# LPC1343.net
KiCad netlist of a schematic drawn in Altium Designer
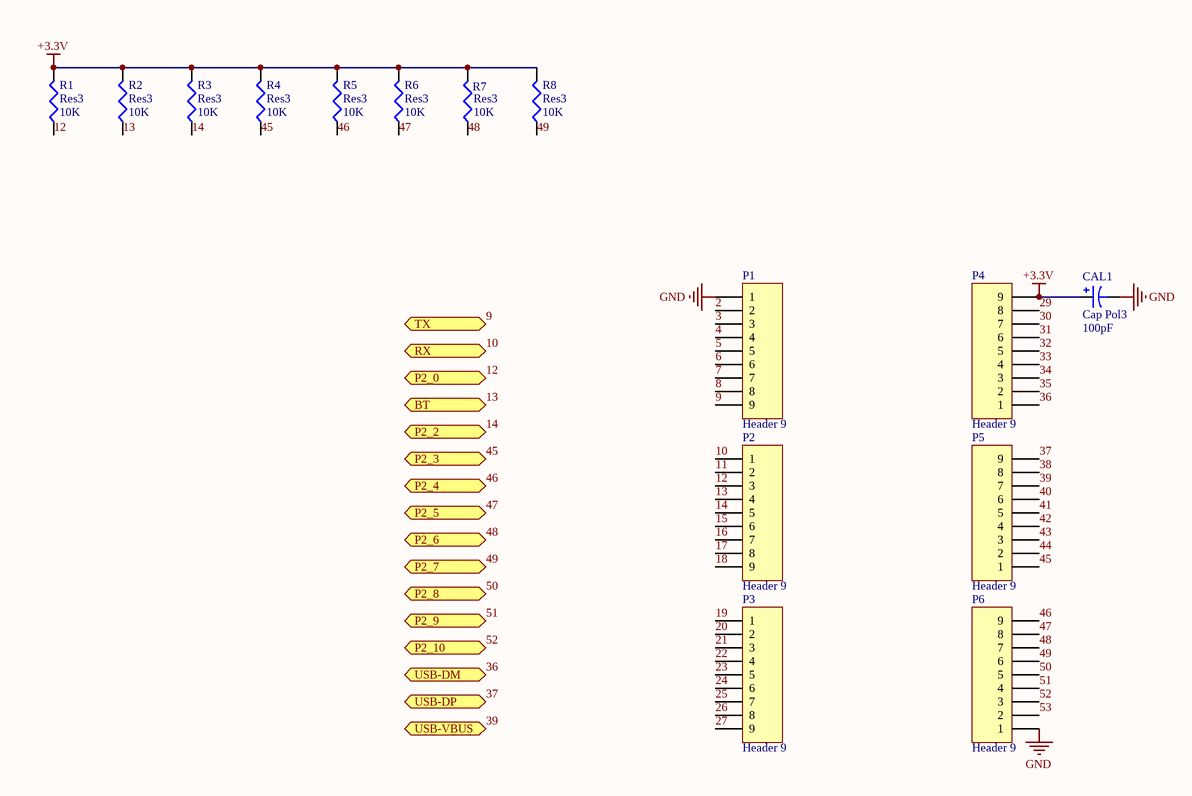
[diagram p0: LPC1343.SchDoc]

(export (version "E")
  (design (tool "Eeschema 10.0.6"))
  (components
    (comp (ref "CAL1")
      (value "Cap Pol3")
      (footprint "C0805")
      (description "Polarized Capacitor (Surface Mount)")
      (fields (field (name "ALTIUM_VALUE") "100pF") (field (name "PUBLISHER") "Altium Limited"))
      (libsource (lib "Miscellaneous Devices") (part "Cap Pol3"))
    )
    (comp (ref "P1")
      (value "Header 9")
      (footprint "HDR1X9")
      (description "Header, 9-Pin")
      (fields (field (name "PUBLISHER") "Altium Limited"))
      (libsource (lib "") (part "Header 9_1"))
    )
    (comp (ref "P2")
      (value "Header 9")
      (footprint "HDR1X9")
      (description "Header, 9-Pin")
      (fields (field (name "PUBLISHER") "Altium Limited"))
      (libsource (lib "") (part "Header 9_1"))
    )
    (comp (ref "P3")
      (value "Header 9")
      (footprint "HDR1X9")
      (description "Header, 9-Pin")
      (fields (field (name "PUBLISHER") "Altium Limited"))
      (libsource (lib "") (part "Header 9_1"))
    )
    (comp (ref "P4")
      (value "Header 9")
      (footprint "HDR1X9")
      (description "Header, 9-Pin")
      (fields (field (name "PUBLISHER") "Altium Limited"))
      (libsource (lib "Miscellaneous Connectors") (part "Header 9"))
    )
    (comp (ref "P5")
      (value "Header 9")
      (footprint "HDR1X9")
      (description "Header, 9-Pin")
      (fields (field (name "PUBLISHER") "Altium Limited"))
      (libsource (lib "Miscellaneous Connectors") (part "Header 9"))
    )
    (comp (ref "P6")
      (value "Header 9")
      (footprint "HDR1X9")
      (description "Header, 9-Pin")
      (fields (field (name "PUBLISHER") "Altium Limited"))
      (libsource (lib "Miscellaneous Connectors") (part "Header 9"))
    )
    (comp (ref "R1")
      (value "Res3")
      (footprint "2012[0805]")
      (description "Resistor")
      (fields (field (name "ALTIUM_VALUE") "10K") (field (name "PUBLISHER") "Altium Limited"))
      (libsource (lib "Miscellaneous Devices") (part "Res3"))
    )
    (comp (ref "R2")
      (value "Res3")
      (footprint "2012[0805]")
      (description "Resistor")
      (fields (field (name "ALTIUM_VALUE") "10K") (field (name "PUBLISHER") "Altium Limited"))
      (libsource (lib "Miscellaneous Devices") (part "Res3"))
    )
    (comp (ref "R3")
      (value "Res3")
      (footprint "2012[0805]")
      (description "Resistor")
      (fields (field (name "ALTIUM_VALUE") "10K") (field (name "PUBLISHER") "Altium Limited"))
      (libsource (lib "Miscellaneous Devices") (part "Res3"))
    )
    (comp (ref "R4")
      (value "Res3")
      (footprint "2012[0805]")
      (description "Resistor")
      (fields (field (name "ALTIUM_VALUE") "10K") (field (name "PUBLISHER") "Altium Limited"))
      (libsource (lib "Miscellaneous Devices") (part "Res3"))
    )
    (comp (ref "R5")
      (value "Res3")
      (footprint "2012[0805]")
      (description "Resistor")
      (fields (field (name "ALTIUM_VALUE") "10K") (field (name "PUBLISHER") "Altium Limited"))
      (libsource (lib "Miscellaneous Devices") (part "Res3"))
    )
    (comp (ref "R6")
      (value "Res3")
      (footprint "2012[0805]")
      (description "Resistor")
      (fields (field (name "ALTIUM_VALUE") "10K") (field (name "PUBLISHER") "Altium Limited"))
      (libsource (lib "Miscellaneous Devices") (part "Res3"))
    )
    (comp (ref "R7")
      (value "Res3")
      (footprint "2012[0805]")
      (description "Resistor")
      (fields (field (name "ALTIUM_VALUE") "10K") (field (name "PUBLISHER") "Altium Limited"))
      (libsource (lib "Miscellaneous Devices") (part "Res3"))
    )
    (comp (ref "R8")
      (value "Res3")
      (footprint "2012[0805]")
      (description "Resistor")
      (fields (field (name "ALTIUM_VALUE") "10K") (field (name "PUBLISHER") "Altium Limited"))
      (libsource (lib "Miscellaneous Devices") (part "Res3"))
    )
  )
  (nets
    (net (code "1") (name "+3.3V") (class "Default")
      (node (ref "CAL1") (pin "1") (pinfunction "1_1") (pintype "passive"))
      (node (ref "P4") (pin "9") (pinfunction "9_9") (pintype "passive"))
      (node (ref "R1") (pin "2") (pinfunction "2_2") (pintype "passive"))
      (node (ref "R2") (pin "2") (pinfunction "2_2") (pintype "passive"))
      (node (ref "R3") (pin "2") (pinfunction "2_2") (pintype "passive"))
      (node (ref "R4") (pin "2") (pinfunction "2_2") (pintype "passive"))
      (node (ref "R5") (pin "2") (pinfunction "2_2") (pintype "passive"))
      (node (ref "R6") (pin "2") (pinfunction "2_2") (pintype "passive"))
      (node (ref "R7") (pin "2") (pinfunction "2_2") (pintype "passive"))
      (node (ref "R8") (pin "2") (pinfunction "2_2") (pintype "passive"))
    )
    (net (code "2") (name "/2") (class "Default")
      (node (ref "P1") (pin "2") (pinfunction "2_2") (pintype "passive"))
    )
    (net (code "3") (name "/3") (class "Default")
      (node (ref "P1") (pin "3") (pinfunction "3_3") (pintype "passive"))
    )
    (net (code "4") (name "/4") (class "Default")
      (node (ref "P1") (pin "4") (pinfunction "4_4") (pintype "passive"))
    )
    (net (code "5") (name "/5") (class "Default")
      (node (ref "P1") (pin "5") (pinfunction "5_5") (pintype "passive"))
    )
    (net (code "6") (name "/6") (class "Default")
      (node (ref "P1") (pin "6") (pinfunction "6_6") (pintype "passive"))
    )
    (net (code "7") (name "/7") (class "Default")
      (node (ref "P1") (pin "7") (pinfunction "7_7") (pintype "passive"))
    )
    (net (code "8") (name "/8") (class "Default")
      (node (ref "P1") (pin "8") (pinfunction "8_8") (pintype "passive"))
    )
    (net (code "9") (name "/9") (class "Default")
      (node (ref "P1") (pin "9") (pinfunction "9_9") (pintype "passive"))
    )
    (net (code "10") (name "/10") (class "Default")
      (node (ref "P2") (pin "1") (pinfunction "1_1") (pintype "passive"))
    )
    (net (code "11") (name "/11") (class "Default")
      (node (ref "P2") (pin "2") (pinfunction "2_2") (pintype "passive"))
    )
    (net (code "12") (name "/12") (class "Default")
      (node (ref "P2") (pin "3") (pinfunction "3_3") (pintype "passive"))
      (node (ref "R1") (pin "1") (pinfunction "1_1") (pintype "passive"))
    )
    (net (code "13") (name "/13") (class "Default")
      (node (ref "P2") (pin "4") (pinfunction "4_4") (pintype "passive"))
      (node (ref "R2") (pin "1") (pinfunction "1_1") (pintype "passive"))
    )
    (net (code "14") (name "/14") (class "Default")
      (node (ref "P2") (pin "5") (pinfunction "5_5") (pintype "passive"))
      (node (ref "R3") (pin "1") (pinfunction "1_1") (pintype "passive"))
    )
    (net (code "15") (name "/15") (class "Default")
      (node (ref "P2") (pin "6") (pinfunction "6_6") (pintype "passive"))
    )
    (net (code "16") (name "/16") (class "Default")
      (node (ref "P2") (pin "7") (pinfunction "7_7") (pintype "passive"))
    )
    (net (code "17") (name "/17") (class "Default")
      (node (ref "P2") (pin "8") (pinfunction "8_8") (pintype "passive"))
    )
    (net (code "18") (name "/18") (class "Default")
      (node (ref "P2") (pin "9") (pinfunction "9_9") (pintype "passive"))
    )
    (net (code "19") (name "/19") (class "Default")
      (node (ref "P3") (pin "1") (pinfunction "1_1") (pintype "passive"))
    )
    (net (code "20") (name "/20") (class "Default")
      (node (ref "P3") (pin "2") (pinfunction "2_2") (pintype "passive"))
    )
    (net (code "21") (name "/21") (class "Default")
      (node (ref "P3") (pin "3") (pinfunction "3_3") (pintype "passive"))
    )
    (net (code "22") (name "/22") (class "Default")
      (node (ref "P3") (pin "4") (pinfunction "4_4") (pintype "passive"))
    )
    (net (code "23") (name "/23") (class "Default")
      (node (ref "P3") (pin "5") (pinfunction "5_5") (pintype "passive"))
    )
    (net (code "24") (name "/24") (class "Default")
      (node (ref "P3") (pin "6") (pinfunction "6_6") (pintype "passive"))
    )
    (net (code "25") (name "/25") (class "Default")
      (node (ref "P3") (pin "7") (pinfunction "7_7") (pintype "passive"))
    )
    (net (code "26") (name "/26") (class "Default")
      (node (ref "P3") (pin "8") (pinfunction "8_8") (pintype "passive"))
    )
    (net (code "27") (name "/27") (class "Default")
      (node (ref "P3") (pin "9") (pinfunction "9_9") (pintype "passive"))
    )
    (net (code "28") (name "/29") (class "Default")
      (node (ref "P4") (pin "8") (pinfunction "8_8") (pintype "passive"))
    )
    (net (code "29") (name "/30") (class "Default")
      (node (ref "P4") (pin "7") (pinfunction "7_7") (pintype "passive"))
    )
    (net (code "30") (name "/31") (class "Default")
      (node (ref "P4") (pin "6") (pinfunction "6_6") (pintype "passive"))
    )
    (net (code "31") (name "/32") (class "Default")
      (node (ref "P4") (pin "5") (pinfunction "5_5") (pintype "passive"))
    )
    (net (code "32") (name "/33") (class "Default")
      (node (ref "P4") (pin "4") (pinfunction "4_4") (pintype "passive"))
    )
    (net (code "33") (name "/34") (class "Default")
      (node (ref "P4") (pin "3") (pinfunction "3_3") (pintype "passive"))
    )
    (net (code "34") (name "/35") (class "Default")
      (node (ref "P4") (pin "2") (pinfunction "2_2") (pintype "passive"))
    )
    (net (code "35") (name "/36") (class "Default")
      (node (ref "P4") (pin "1") (pinfunction "1_1") (pintype "passive"))
    )
    (net (code "36") (name "/37") (class "Default")
      (node (ref "P5") (pin "9") (pinfunction "9_9") (pintype "passive"))
    )
    (net (code "37") (name "/38") (class "Default")
      (node (ref "P5") (pin "8") (pinfunction "8_8") (pintype "passive"))
    )
    (net (code "38") (name "/39") (class "Default")
      (node (ref "P5") (pin "7") (pinfunction "7_7") (pintype "passive"))
    )
    (net (code "39") (name "/40") (class "Default")
      (node (ref "P5") (pin "6") (pinfunction "6_6") (pintype "passive"))
    )
    (net (code "40") (name "/41") (class "Default")
      (node (ref "P5") (pin "5") (pinfunction "5_5") (pintype "passive"))
    )
    (net (code "41") (name "/42") (class "Default")
      (node (ref "P5") (pin "4") (pinfunction "4_4") (pintype "passive"))
    )
    (net (code "42") (name "/43") (class "Default")
      (node (ref "P5") (pin "3") (pinfunction "3_3") (pintype "passive"))
    )
    (net (code "43") (name "/44") (class "Default")
      (node (ref "P5") (pin "2") (pinfunction "2_2") (pintype "passive"))
    )
    (net (code "44") (name "/45") (class "Default")
      (node (ref "P5") (pin "1") (pinfunction "1_1") (pintype "passive"))
      (node (ref "R4") (pin "1") (pinfunction "1_1") (pintype "passive"))
    )
    (net (code "45") (name "/46") (class "Default")
      (node (ref "P6") (pin "9") (pinfunction "9_9") (pintype "passive"))
      (node (ref "R5") (pin "1") (pinfunction "1_1") (pintype "passive"))
    )
    (net (code "46") (name "/47") (class "Default")
      (node (ref "P6") (pin "8") (pinfunction "8_8") (pintype "passive"))
      (node (ref "R6") (pin "1") (pinfunction "1_1") (pintype "passive"))
    )
    (net (code "47") (name "/48") (class "Default")
      (node (ref "P6") (pin "7") (pinfunction "7_7") (pintype "passive"))
      (node (ref "R7") (pin "1") (pinfunction "1_1") (pintype "passive"))
    )
    (net (code "48") (name "/49") (class "Default")
      (node (ref "P6") (pin "6") (pinfunction "6_6") (pintype "passive"))
      (node (ref "R8") (pin "1") (pinfunction "1_1") (pintype "passive"))
    )
    (net (code "49") (name "/50") (class "Default")
      (node (ref "P6") (pin "5") (pinfunction "5_5") (pintype "passive"))
    )
    (net (code "50") (name "/51") (class "Default")
      (node (ref "P6") (pin "4") (pinfunction "4_4") (pintype "passive"))
    )
    (net (code "51") (name "/52") (class "Default")
      (node (ref "P6") (pin "3") (pinfunction "3_3") (pintype "passive"))
    )
    (net (code "52") (name "/53") (class "Default")
      (node (ref "P6") (pin "2") (pinfunction "2_2") (pintype "passive"))
    )
    (net (code "53") (name "GND") (class "Default")
      (node (ref "CAL1") (pin "2") (pinfunction "2_2") (pintype "passive"))
      (node (ref "P1") (pin "1") (pinfunction "1_1") (pintype "passive"))
      (node (ref "P6") (pin "1") (pinfunction "1_1") (pintype "passive"))
    )
  )
)
